# DarkPill_V1_1.net
KiCad netlist of a schematic drawn in EAGLE
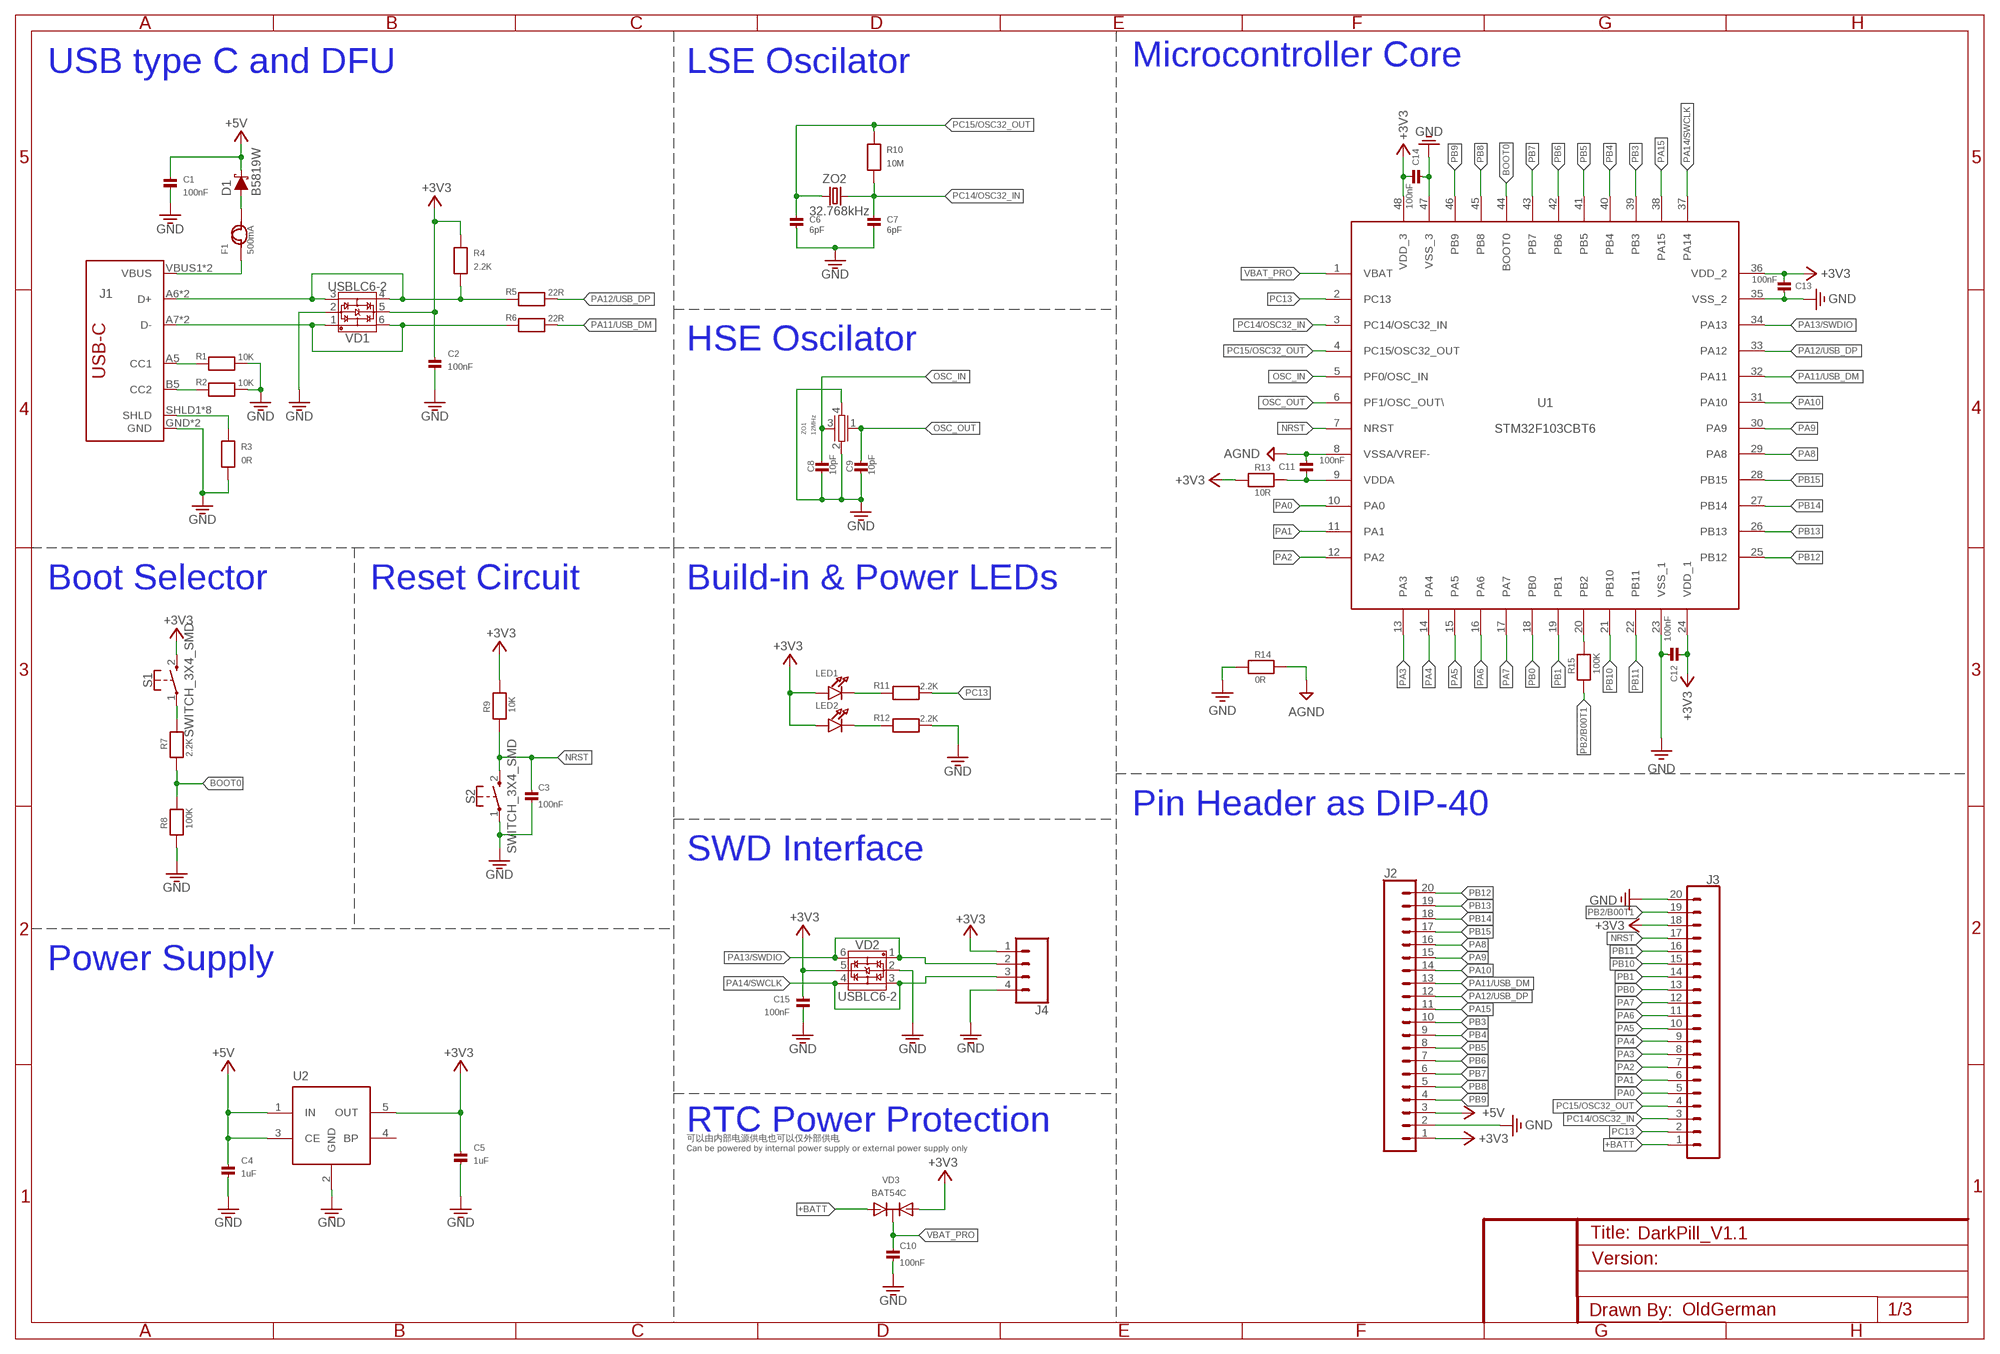
[diagram p0: schematic, sheet 1]

(export (version "E")
  (design (tool "Eeschema 10.0.6"))
  (components
    (comp (ref "C1")
      (value "100nF")
      (footprint "eagle-import:0603")
      (libsource (lib "eagle-import") (part "CAP_CERAMIC0603"))
    )
    (comp (ref "C2")
      (value "100nF")
      (footprint "eagle-import:0603")
      (libsource (lib "eagle-import") (part "CAP_CERAMIC0603"))
    )
    (comp (ref "C3")
      (value "100nF")
      (footprint "eagle-import:0603")
      (libsource (lib "eagle-import") (part "CAP_CERAMIC0603"))
    )
    (comp (ref "C4")
      (value "1uF")
      (footprint "eagle-import:0603")
      (libsource (lib "eagle-import") (part "CAP_CERAMIC0603"))
    )
    (comp (ref "C5")
      (value "1uF")
      (footprint "eagle-import:0603")
      (libsource (lib "eagle-import") (part "CAP_CERAMIC0603"))
    )
    (comp (ref "C6")
      (value "6pF")
      (footprint "eagle-import:0603")
      (libsource (lib "eagle-import") (part "CAP_CERAMIC0603"))
    )
    (comp (ref "C7")
      (value "6pF")
      (footprint "eagle-import:0603")
      (libsource (lib "eagle-import") (part "CAP_CERAMIC0603"))
    )
    (comp (ref "C8")
      (value "10pF")
      (footprint "eagle-import:0603")
      (libsource (lib "eagle-import") (part "CAP_CERAMIC0603"))
    )
    (comp (ref "C9")
      (value "10pF")
      (footprint "eagle-import:0603")
      (libsource (lib "eagle-import") (part "CAP_CERAMIC0603"))
    )
    (comp (ref "C10")
      (value "100nF")
      (footprint "eagle-import:0603")
      (libsource (lib "eagle-import") (part "CAP_CERAMIC0603"))
    )
    (comp (ref "C11")
      (value "100nF")
      (footprint "eagle-import:0603")
      (libsource (lib "eagle-import") (part "CAP_CERAMIC0603"))
    )
    (comp (ref "C12")
      (value "100nF")
      (footprint "eagle-import:0603")
      (libsource (lib "eagle-import") (part "CAP_CERAMIC0603"))
    )
    (comp (ref "C13")
      (value "100nF")
      (footprint "eagle-import:0603")
      (libsource (lib "eagle-import") (part "CAP_CERAMIC0603"))
    )
    (comp (ref "C14")
      (value "100nF")
      (footprint "eagle-import:0603")
      (libsource (lib "eagle-import") (part "CAP_CERAMIC0603"))
    )
    (comp (ref "C15")
      (value "100nF")
      (footprint "eagle-import:0603")
      (libsource (lib "eagle-import") (part "CAP_CERAMIC0603"))
    )
    (comp (ref "D1")
      (value "B5819W")
      (footprint "eagle-import:SOD-323")
      (libsource (lib "eagle-import") (part "B5819W-SOD323"))
    )
    (comp (ref "F1")
      (value "500mA")
      (footprint "eagle-import:0603")
      (libsource (lib "eagle-import") (part "FUSE"))
    )
    (comp (ref "J1")
      (value "USB_C2-LAYER")
      (footprint "eagle-import:USB-C-16P")
      (libsource (lib "eagle-import") (part "USB_C2-LAYER"))
    )
    (comp (ref "J2")
      (value "CONN_20")
      (footprint "eagle-import:1X20")
      (libsource (lib "eagle-import") (part "CONN_20"))
    )
    (comp (ref "J3")
      (value "CONN_20")
      (footprint "eagle-import:1X20")
      (libsource (lib "eagle-import") (part "CONN_20"))
    )
    (comp (ref "J4")
      (value "CONN_04PTH")
      (footprint "eagle-import:1X04")
      (libsource (lib "eagle-import") (part "CONN_04PTH"))
    )
    (comp (ref "LED1")
      (value "LED_0603_MICRO")
      (footprint "eagle-import:0603_LED")
      (libsource (lib "eagle-import") (part "LED_0603_MICRO"))
    )
    (comp (ref "LED2")
      (value "LED_0603_MICRO")
      (footprint "eagle-import:0603_LED")
      (libsource (lib "eagle-import") (part "LED_0603_MICRO"))
    )
    (comp (ref "R1")
      (value "10K")
      (footprint "eagle-import:0603")
      (libsource (lib "eagle-import") (part "RESISTOR0603"))
    )
    (comp (ref "R2")
      (value "10K")
      (footprint "eagle-import:0603")
      (libsource (lib "eagle-import") (part "RESISTOR0603"))
    )
    (comp (ref "R3")
      (value "0R")
      (footprint "eagle-import:0603")
      (libsource (lib "eagle-import") (part "RESISTOR0603"))
    )
    (comp (ref "R4")
      (value "2.2K")
      (footprint "eagle-import:0603")
      (libsource (lib "eagle-import") (part "RESISTOR0603"))
    )
    (comp (ref "R5")
      (value "22R")
      (footprint "eagle-import:0603")
      (libsource (lib "eagle-import") (part "RESISTOR0603"))
    )
    (comp (ref "R6")
      (value "22R")
      (footprint "eagle-import:0603")
      (libsource (lib "eagle-import") (part "RESISTOR0603"))
    )
    (comp (ref "R7")
      (value "2.2K")
      (footprint "eagle-import:0603")
      (libsource (lib "eagle-import") (part "RESISTOR0603"))
    )
    (comp (ref "R8")
      (value "100K")
      (footprint "eagle-import:0603")
      (libsource (lib "eagle-import") (part "RESISTOR0603"))
    )
    (comp (ref "R9")
      (value "10K")
      (footprint "eagle-import:0603")
      (libsource (lib "eagle-import") (part "RESISTOR0603"))
    )
    (comp (ref "R10")
      (value "10M")
      (footprint "eagle-import:0603")
      (libsource (lib "eagle-import") (part "RESISTOR0603"))
    )
    (comp (ref "R11")
      (value "2.2K")
      (footprint "eagle-import:0603")
      (libsource (lib "eagle-import") (part "RESISTOR0603"))
    )
    (comp (ref "R12")
      (value "2.2K")
      (footprint "eagle-import:0603")
      (libsource (lib "eagle-import") (part "RESISTOR0603"))
    )
    (comp (ref "R13")
      (value "10R")
      (footprint "eagle-import:0603")
      (libsource (lib "eagle-import") (part "RESISTOR0603"))
    )
    (comp (ref "R14")
      (value "0R")
      (footprint "eagle-import:0603")
      (libsource (lib "eagle-import") (part "RESISTOR0603"))
    )
    (comp (ref "R15")
      (value "100K")
      (footprint "eagle-import:0603")
      (libsource (lib "eagle-import") (part "RESISTOR0603"))
    )
    (comp (ref "S1")
      (value "SWITCH_3X4_SMD")
      (footprint "eagle-import:SWITCH_3X4_SMD")
      (libsource (lib "eagle-import") (part "SWITCH_3X4_SMD"))
    )
    (comp (ref "S2")
      (value "SWITCH_3X4_SMD")
      (footprint "eagle-import:SWITCH_3X4_SMD")
      (libsource (lib "eagle-import") (part "SWITCH_3X4_SMD"))
    )
    (comp (ref "U1")
      (value "STM32F103CBT6")
      (footprint "eagle-import:TQFP48")
      (libsource (lib "eagle-import") (part "STM32F303CBT6"))
    )
    (comp (ref "U2")
      (value "ME6211C33M5G-N")
      (footprint "eagle-import:SOT23-5")
      (libsource (lib "eagle-import") (part "ME6211C33M5G-N"))
    )
    (comp (ref "VD1")
      (value "USBLC6-2")
      (footprint "eagle-import:SOT23-6")
      (libsource (lib "eagle-import") (part "USBLC6-2SOT23-6"))
    )
    (comp (ref "VD2")
      (value "USBLC6-2")
      (footprint "eagle-import:SOT23-6")
      (libsource (lib "eagle-import") (part "USBLC6-2SOT23-6"))
    )
    (comp (ref "VD3")
      (value "BAT54C")
      (footprint "eagle-import:SOT23-R")
      (libsource (lib "eagle-import") (part "BAT54C"))
    )
    (comp (ref "ZO1")
      (value "12MHz")
      (footprint "eagle-import:3.2X2.5_KX-7")
      (libsource (lib "eagle-import") (part "3225_CRYSTALL"))
    )
    (comp (ref "ZO2")
      (value "32.768kHz")
      (footprint "eagle-import:3.2X1.5")
      (libsource (lib "eagle-import") (part "KX-327-NHF"))
    )
  )
  (nets
    (net (code "1") (name "+3V3") (class "Default")
      (node (ref "C12") (pin "2") (pinfunction "P$2_2") (pintype "passive"))
      (node (ref "C13") (pin "2") (pinfunction "P$2_2") (pintype "passive"))
      (node (ref "C14") (pin "2") (pinfunction "P$2_2") (pintype "passive"))
      (node (ref "C15") (pin "1") (pinfunction "P$1_1") (pintype "passive"))
      (node (ref "C2") (pin "1") (pinfunction "P$1_1") (pintype "passive"))
      (node (ref "C5") (pin "1") (pinfunction "P$1_1") (pintype "passive"))
      (node (ref "J2") (pin "1") (pinfunction "1_1") (pintype "passive"))
      (node (ref "J3") (pin "18") (pinfunction "18_18") (pintype "passive"))
      (node (ref "J4") (pin "1") (pinfunction "1_1") (pintype "passive"))
      (node (ref "LED1") (pin "1") (pinfunction "A_1") (pintype "passive"))
      (node (ref "LED2") (pin "1") (pinfunction "A_1") (pintype "passive"))
      (node (ref "R13") (pin "2") (pinfunction "2_2") (pintype "passive"))
      (node (ref "R4") (pin "2") (pinfunction "2_2") (pintype "passive"))
      (node (ref "R9") (pin "1") (pinfunction "1_1") (pintype "passive"))
      (node (ref "S1") (pin "2") (pinfunction "2_2") (pintype "passive"))
      (node (ref "U1") (pin "24") (pinfunction "VDD_1_24") (pintype "bidirectional"))
      (node (ref "U1") (pin "36") (pinfunction "VDD_2_36") (pintype "bidirectional"))
      (node (ref "U1") (pin "48") (pinfunction "VDD_3_48") (pintype "bidirectional"))
      (node (ref "U2") (pin "5") (pinfunction "OUT_5") (pintype "bidirectional"))
      (node (ref "VD1") (pin "5") (pinfunction "P$5_5") (pintype "bidirectional"))
      (node (ref "VD2") (pin "5") (pinfunction "P$5_5") (pintype "bidirectional"))
      (node (ref "VD3") (pin "1") (pinfunction "A1_1") (pintype "passive"))
    )
    (net (code "2") (name "+5V") (class "Default")
      (node (ref "C1") (pin "1") (pinfunction "P$1_1") (pintype "passive"))
      (node (ref "C4") (pin "1") (pinfunction "P$1_1") (pintype "passive"))
      (node (ref "D1") (pin "C") (pinfunction "C_C") (pintype "passive"))
      (node (ref "J2") (pin "3") (pinfunction "3_3") (pintype "passive"))
      (node (ref "U2") (pin "1") (pinfunction "IN_1") (pintype "bidirectional"))
      (node (ref "U2") (pin "3") (pinfunction "CE_3") (pintype "bidirectional"))
    )
    (net (code "3") (name "+BATT") (class "Default")
      (node (ref "J3") (pin "1") (pinfunction "1_1") (pintype "passive"))
      (node (ref "VD3") (pin "2") (pinfunction "A2_2") (pintype "passive"))
    )
    (net (code "4") (name "AGND") (class "Default")
      (node (ref "C11") (pin "1") (pinfunction "P$1_1") (pintype "passive"))
      (node (ref "R14") (pin "1") (pinfunction "1_1") (pintype "passive"))
      (node (ref "U1") (pin "8") (pinfunction "VSSA/VREF-_8") (pintype "bidirectional"))
    )
    (net (code "5") (name "BOOT0") (class "Default")
      (node (ref "R7") (pin "1") (pinfunction "1_1") (pintype "passive"))
      (node (ref "R8") (pin "1") (pinfunction "1_1") (pintype "passive"))
      (node (ref "U1") (pin "44") (pinfunction "BOOT0_44") (pintype "bidirectional"))
    )
    (net (code "6") (name "GND") (class "Default")
      (node (ref "C1") (pin "2") (pinfunction "P$2_2") (pintype "passive"))
      (node (ref "C10") (pin "2") (pinfunction "P$2_2") (pintype "passive"))
      (node (ref "C12") (pin "1") (pinfunction "P$1_1") (pintype "passive"))
      (node (ref "C13") (pin "1") (pinfunction "P$1_1") (pintype "passive"))
      (node (ref "C14") (pin "1") (pinfunction "P$1_1") (pintype "passive"))
      (node (ref "C15") (pin "2") (pinfunction "P$2_2") (pintype "passive"))
      (node (ref "C2") (pin "2") (pinfunction "P$2_2") (pintype "passive"))
      (node (ref "C3") (pin "2") (pinfunction "P$2_2") (pintype "passive"))
      (node (ref "C4") (pin "2") (pinfunction "P$2_2") (pintype "passive"))
      (node (ref "C5") (pin "2") (pinfunction "P$2_2") (pintype "passive"))
      (node (ref "C6") (pin "1") (pinfunction "P$1_1") (pintype "passive"))
      (node (ref "C7") (pin "1") (pinfunction "P$1_1") (pintype "passive"))
      (node (ref "C8") (pin "1") (pinfunction "P$1_1") (pintype "passive"))
      (node (ref "C9") (pin "1") (pinfunction "P$1_1") (pintype "passive"))
      (node (ref "J1") (pin "GND") (pinfunction "GND_GND") (pintype "bidirectional"))
      (node (ref "J1") (pin "GND2") (pinfunction "GND_GND2") (pintype "bidirectional"))
      (node (ref "J2") (pin "2") (pinfunction "2_2") (pintype "passive"))
      (node (ref "J3") (pin "20") (pinfunction "20_20") (pintype "passive"))
      (node (ref "J4") (pin "4") (pinfunction "4_4") (pintype "passive"))
      (node (ref "R1") (pin "2") (pinfunction "2_2") (pintype "passive"))
      (node (ref "R12") (pin "2") (pinfunction "2_2") (pintype "passive"))
      (node (ref "R14") (pin "2") (pinfunction "2_2") (pintype "passive"))
      (node (ref "R2") (pin "2") (pinfunction "2_2") (pintype "passive"))
      (node (ref "R3") (pin "1") (pinfunction "1_1") (pintype "passive"))
      (node (ref "R8") (pin "2") (pinfunction "2_2") (pintype "passive"))
      (node (ref "S2") (pin "1") (pinfunction "1_1") (pintype "passive"))
      (node (ref "U1") (pin "23") (pinfunction "VSS_1_23") (pintype "bidirectional"))
      (node (ref "U1") (pin "35") (pinfunction "VSS_2_35") (pintype "bidirectional"))
      (node (ref "U1") (pin "47") (pinfunction "VSS_3_47") (pintype "bidirectional"))
      (node (ref "U2") (pin "2") (pinfunction "GND_2") (pintype "bidirectional"))
      (node (ref "VD1") (pin "2") (pinfunction "P$2_2") (pintype "bidirectional"))
      (node (ref "VD2") (pin "2") (pinfunction "P$2_2") (pintype "bidirectional"))
      (node (ref "ZO1") (pin "2") (pinfunction "P$3_2") (pintype "power_in"))
      (node (ref "ZO1") (pin "4") (pinfunction "P$4_4") (pintype "power_in"))
    )
    (net (code "7") (name "NRST") (class "Default")
      (node (ref "C3") (pin "1") (pinfunction "P$1_1") (pintype "passive"))
      (node (ref "J3") (pin "17") (pinfunction "17_17") (pintype "passive"))
      (node (ref "R9") (pin "2") (pinfunction "2_2") (pintype "passive"))
      (node (ref "S2") (pin "2") (pinfunction "2_2") (pintype "passive"))
      (node (ref "U1") (pin "7") (pinfunction "NRST_7") (pintype "bidirectional"))
    )
    (net (code "8") (name "Net-(C11-P$2)") (class "Default")
      (node (ref "C11") (pin "2") (pinfunction "P$2_2") (pintype "passive"))
      (node (ref "R13") (pin "1") (pinfunction "1_1") (pintype "passive"))
      (node (ref "U1") (pin "9") (pinfunction "VDDA_9") (pintype "bidirectional"))
    )
    (net (code "9") (name "Net-(D1-PadA)") (class "Default")
      (node (ref "D1") (pin "A") (pinfunction "A_A") (pintype "passive"))
      (node (ref "F1") (pin "2") (pinfunction "2_2") (pintype "bidirectional"))
    )
    (net (code "10") (name "Net-(F1-Pad1)") (class "Default")
      (node (ref "F1") (pin "1") (pinfunction "1_1") (pintype "bidirectional"))
      (node (ref "J1") (pin "VBUS1") (pinfunction "VBUS_VBUS1") (pintype "bidirectional"))
      (node (ref "J1") (pin "VBUS2") (pinfunction "VBUS_VBUS2") (pintype "bidirectional"))
    )
    (net (code "11") (name "Net-(J1-CC1)") (class "Default")
      (node (ref "J1") (pin "A5") (pinfunction "CC1_A5") (pintype "bidirectional"))
      (node (ref "R1") (pin "1") (pinfunction "1_1") (pintype "passive"))
    )
    (net (code "12") (name "Net-(J1-CC2)") (class "Default")
      (node (ref "J1") (pin "B5") (pinfunction "CC2_B5") (pintype "bidirectional"))
      (node (ref "R2") (pin "1") (pinfunction "1_1") (pintype "passive"))
    )
    (net (code "13") (name "Net-(J1-SHLD-PadSHLD1)") (class "Default")
      (node (ref "J1") (pin "SHLD1") (pinfunction "SHLD_SHLD1") (pintype "bidirectional"))
      (node (ref "J1") (pin "SHLD2") (pinfunction "SHLD_SHLD2") (pintype "bidirectional"))
      (node (ref "J1") (pin "SHLD3") (pinfunction "SHLD_SHLD3") (pintype "bidirectional"))
      (node (ref "J1") (pin "SHLD4") (pinfunction "SHLD_SHLD4") (pintype "bidirectional"))
      (node (ref "J1") (pin "SHLD5") (pinfunction "SHLD_SHLD5") (pintype "bidirectional"))
      (node (ref "J1") (pin "SHLD6") (pinfunction "SHLD_SHLD6") (pintype "bidirectional"))
      (node (ref "J1") (pin "SHLD7") (pinfunction "SHLD_SHLD7") (pintype "bidirectional"))
      (node (ref "J1") (pin "SHLD8") (pinfunction "SHLD_SHLD8") (pintype "bidirectional"))
      (node (ref "R3") (pin "2") (pinfunction "2_2") (pintype "passive"))
    )
    (net (code "14") (name "Net-(LED1-C)") (class "Default")
      (node (ref "LED1") (pin "2") (pinfunction "C_2") (pintype "passive"))
      (node (ref "R11") (pin "1") (pinfunction "1_1") (pintype "passive"))
    )
    (net (code "15") (name "Net-(LED2-C)") (class "Default")
      (node (ref "LED2") (pin "2") (pinfunction "C_2") (pintype "passive"))
      (node (ref "R12") (pin "1") (pinfunction "1_1") (pintype "passive"))
    )
    (net (code "16") (name "Net-(R7-Pad2)") (class "Default")
      (node (ref "R7") (pin "2") (pinfunction "2_2") (pintype "passive"))
      (node (ref "S1") (pin "1") (pinfunction "1_1") (pintype "passive"))
    )
    (net (code "17") (name "Net-(U1-PB2)") (class "Default")
      (node (ref "R15") (pin "1") (pinfunction "1_1") (pintype "passive"))
      (node (ref "U1") (pin "20") (pinfunction "PB2_20") (pintype "bidirectional"))
    )
    (net (code "18") (name "Net-(VD1-P$1)") (class "Default")
      (node (ref "J1") (pin "A7") (pinfunction "D-_A7") (pintype "bidirectional"))
      (node (ref "J1") (pin "B7") (pinfunction "D-_B7") (pintype "bidirectional"))
      (node (ref "R6") (pin "1") (pinfunction "1_1") (pintype "passive"))
      (node (ref "VD1") (pin "1") (pinfunction "P$1_1") (pintype "bidirectional"))
      (node (ref "VD1") (pin "6") (pinfunction "P$6_6") (pintype "bidirectional"))
    )
    (net (code "19") (name "Net-(VD1-P$3)") (class "Default")
      (node (ref "J1") (pin "A6") (pinfunction "D+_A6") (pintype "bidirectional"))
      (node (ref "J1") (pin "B6") (pinfunction "D+_B6") (pintype "bidirectional"))
      (node (ref "R4") (pin "1") (pinfunction "1_1") (pintype "passive"))
      (node (ref "R5") (pin "1") (pinfunction "1_1") (pintype "passive"))
      (node (ref "VD1") (pin "3") (pinfunction "P$3_3") (pintype "bidirectional"))
      (node (ref "VD1") (pin "4") (pinfunction "P$4_4") (pintype "bidirectional"))
    )
    (net (code "20") (name "OSC_IN") (class "Default")
      (node (ref "C8") (pin "2") (pinfunction "P$2_2") (pintype "passive"))
      (node (ref "U1") (pin "5") (pinfunction "PF0/OSC_IN_5") (pintype "bidirectional"))
      (node (ref "ZO1") (pin "3") (pinfunction "P$2_3") (pintype "bidirectional"))
    )
    (net (code "21") (name "OSC_OUT") (class "Default")
      (node (ref "C9") (pin "2") (pinfunction "P$2_2") (pintype "passive"))
      (node (ref "U1") (pin "6") (pinfunction "PF1/OSC_OUT\\_6") (pintype "bidirectional"))
      (node (ref "ZO1") (pin "1") (pinfunction "P$1_1") (pintype "bidirectional"))
    )
    (net (code "22") (name "PA0") (class "Default")
      (node (ref "J3") (pin "5") (pinfunction "5_5") (pintype "passive"))
      (node (ref "U1") (pin "10") (pinfunction "PA0_10") (pintype "bidirectional"))
    )
    (net (code "23") (name "PA1") (class "Default")
      (node (ref "J3") (pin "6") (pinfunction "6_6") (pintype "passive"))
      (node (ref "U1") (pin "11") (pinfunction "PA1_11") (pintype "bidirectional"))
    )
    (net (code "24") (name "PA2") (class "Default")
      (node (ref "J3") (pin "7") (pinfunction "7_7") (pintype "passive"))
      (node (ref "U1") (pin "12") (pinfunction "PA2_12") (pintype "bidirectional"))
    )
    (net (code "25") (name "PA3") (class "Default")
      (node (ref "J3") (pin "8") (pinfunction "8_8") (pintype "passive"))
      (node (ref "U1") (pin "13") (pinfunction "PA3_13") (pintype "bidirectional"))
    )
    (net (code "26") (name "PA4") (class "Default")
      (node (ref "J3") (pin "9") (pinfunction "9_9") (pintype "passive"))
      (node (ref "U1") (pin "14") (pinfunction "PA4_14") (pintype "bidirectional"))
    )
    (net (code "27") (name "PA5") (class "Default")
      (node (ref "J3") (pin "10") (pinfunction "10_10") (pintype "passive"))
      (node (ref "U1") (pin "15") (pinfunction "PA5_15") (pintype "bidirectional"))
    )
    (net (code "28") (name "PA6") (class "Default")
      (node (ref "J3") (pin "11") (pinfunction "11_11") (pintype "passive"))
      (node (ref "U1") (pin "16") (pinfunction "PA6_16") (pintype "bidirectional"))
    )
    (net (code "29") (name "PA7") (class "Default")
      (node (ref "J3") (pin "12") (pinfunction "12_12") (pintype "passive"))
      (node (ref "U1") (pin "17") (pinfunction "PA7_17") (pintype "bidirectional"))
    )
    (net (code "30") (name "PA8") (class "Default")
      (node (ref "J2") (pin "16") (pinfunction "16_16") (pintype "passive"))
      (node (ref "U1") (pin "29") (pinfunction "PA8_29") (pintype "bidirectional"))
    )
    (net (code "31") (name "PA9") (class "Default")
      (node (ref "J2") (pin "15") (pinfunction "15_15") (pintype "passive"))
      (node (ref "U1") (pin "30") (pinfunction "PA9_30") (pintype "bidirectional"))
    )
    (net (code "32") (name "PA10") (class "Default")
      (node (ref "J2") (pin "14") (pinfunction "14_14") (pintype "passive"))
      (node (ref "U1") (pin "31") (pinfunction "PA10_31") (pintype "bidirectional"))
    )
    (net (code "33") (name "PA11{slash}USB_DM") (class "Default")
      (node (ref "J2") (pin "13") (pinfunction "13_13") (pintype "passive"))
      (node (ref "R6") (pin "2") (pinfunction "2_2") (pintype "passive"))
      (node (ref "U1") (pin "32") (pinfunction "PA11_32") (pintype "bidirectional"))
    )
    (net (code "34") (name "PA12{slash}USB_DP") (class "Default")
      (node (ref "J2") (pin "12") (pinfunction "12_12") (pintype "passive"))
      (node (ref "R5") (pin "2") (pinfunction "2_2") (pintype "passive"))
      (node (ref "U1") (pin "33") (pinfunction "PA12_33") (pintype "bidirectional"))
    )
    (net (code "35") (name "PA13{slash}SWDIO") (class "Default")
      (node (ref "J4") (pin "2") (pinfunction "2_2") (pintype "passive"))
      (node (ref "U1") (pin "34") (pinfunction "PA13_34") (pintype "bidirectional"))
      (node (ref "VD2") (pin "1") (pinfunction "P$1_1") (pintype "bidirectional"))
      (node (ref "VD2") (pin "6") (pinfunction "P$6_6") (pintype "bidirectional"))
    )
    (net (code "36") (name "PA14{slash}SWCLK") (class "Default")
      (node (ref "J4") (pin "3") (pinfunction "3_3") (pintype "passive"))
      (node (ref "U1") (pin "37") (pinfunction "PA14_37") (pintype "bidirectional"))
      (node (ref "VD2") (pin "3") (pinfunction "P$3_3") (pintype "bidirectional"))
      (node (ref "VD2") (pin "4") (pinfunction "P$4_4") (pintype "bidirectional"))
    )
    (net (code "37") (name "PA15") (class "Default")
      (node (ref "J2") (pin "11") (pinfunction "11_11") (pintype "passive"))
      (node (ref "U1") (pin "38") (pinfunction "PA15_38") (pintype "bidirectional"))
    )
    (net (code "38") (name "PB0") (class "Default")
      (node (ref "J3") (pin "13") (pinfunction "13_13") (pintype "passive"))
      (node (ref "U1") (pin "18") (pinfunction "PB0_18") (pintype "bidirectional"))
    )
    (net (code "39") (name "PB1") (class "Default")
      (node (ref "J3") (pin "14") (pinfunction "14_14") (pintype "passive"))
      (node (ref "U1") (pin "19") (pinfunction "PB1_19") (pintype "bidirectional"))
    )
    (net (code "40") (name "PB2{slash}B00T1") (class "Default")
      (node (ref "J3") (pin "19") (pinfunction "19_19") (pintype "passive"))
      (node (ref "R15") (pin "2") (pinfunction "2_2") (pintype "passive"))
    )
    (net (code "41") (name "PB3") (class "Default")
      (node (ref "J2") (pin "10") (pinfunction "10_10") (pintype "passive"))
      (node (ref "U1") (pin "39") (pinfunction "PB3_39") (pintype "bidirectional"))
    )
    (net (code "42") (name "PB4") (class "Default")
      (node (ref "J2") (pin "9") (pinfunction "9_9") (pintype "passive"))
      (node (ref "U1") (pin "40") (pinfunction "PB4_40") (pintype "bidirectional"))
    )
    (net (code "43") (name "PB5") (class "Default")
      (node (ref "J2") (pin "8") (pinfunction "8_8") (pintype "passive"))
      (node (ref "U1") (pin "41") (pinfunction "PB5_41") (pintype "bidirectional"))
    )
    (net (code "44") (name "PB6") (class "Default")
      (node (ref "J2") (pin "7") (pinfunction "7_7") (pintype "passive"))
      (node (ref "U1") (pin "42") (pinfunction "PB6_42") (pintype "bidirectional"))
    )
    (net (code "45") (name "PB7") (class "Default")
      (node (ref "J2") (pin "6") (pinfunction "6_6") (pintype "passive"))
      (node (ref "U1") (pin "43") (pinfunction "PB7_43") (pintype "bidirectional"))
    )
    (net (code "46") (name "PB8") (class "Default")
      (node (ref "J2") (pin "5") (pinfunction "5_5") (pintype "passive"))
      (node (ref "U1") (pin "45") (pinfunction "PB8_45") (pintype "bidirectional"))
    )
    (net (code "47") (name "PB9") (class "Default")
      (node (ref "J2") (pin "4") (pinfunction "4_4") (pintype "passive"))
      (node (ref "U1") (pin "46") (pinfunction "PB9_46") (pintype "bidirectional"))
    )
    (net (code "48") (name "PB10") (class "Default")
      (node (ref "J3") (pin "15") (pinfunction "15_15") (pintype "passive"))
      (node (ref "U1") (pin "21") (pinfunction "PB10_21") (pintype "bidirectional"))
    )
    (net (code "49") (name "PB11") (class "Default")
      (node (ref "J3") (pin "16") (pinfunction "16_16") (pintype "passive"))
      (node (ref "U1") (pin "22") (pinfunction "PB11_22") (pintype "bidirectional"))
    )
    (net (code "50") (name "PB12") (class "Default")
      (node (ref "J2") (pin "20") (pinfunction "20_20") (pintype "passive"))
      (node (ref "U1") (pin "25") (pinfunction "PB12_25") (pintype "bidirectional"))
    )
    (net (code "51") (name "PB13") (class "Default")
      (node (ref "J2") (pin "19") (pinfunction "19_19") (pintype "passive"))
      (node (ref "U1") (pin "26") (pinfunction "PB13_26") (pintype "bidirectional"))
    )
    (net (code "52") (name "PB14") (class "Default")
      (node (ref "J2") (pin "18") (pinfunction "18_18") (pintype "passive"))
      (node (ref "U1") (pin "27") (pinfunction "PB14_27") (pintype "bidirectional"))
    )
    (net (code "53") (name "PB15") (class "Default")
      (node (ref "J2") (pin "17") (pinfunction "17_17") (pintype "passive"))
      (node (ref "U1") (pin "28") (pinfunction "PB15_28") (pintype "bidirectional"))
    )
    (net (code "54") (name "PC13") (class "Default")
      (node (ref "J3") (pin "2") (pinfunction "2_2") (pintype "passive"))
      (node (ref "R11") (pin "2") (pinfunction "2_2") (pintype "passive"))
      (node (ref "U1") (pin "2") (pinfunction "PC13_2") (pintype "bidirectional"))
    )
    (net (code "55") (name "PC14{slash}OSC32_IN") (class "Default")
      (node (ref "C7") (pin "2") (pinfunction "P$2_2") (pintype "passive"))
      (node (ref "J3") (pin "3") (pinfunction "3_3") (pintype "passive"))
      (node (ref "R10") (pin "2") (pinfunction "2_2") (pintype "passive"))
      (node (ref "U1") (pin "3") (pinfunction "PC14/OSC32_IN_3") (pintype "bidirectional"))
      (node (ref "ZO2") (pin "2") (pinfunction "2_2") (pintype "passive"))
    )
    (net (code "56") (name "PC15{slash}OSC32_OUT") (class "Default")
      (node (ref "C6") (pin "2") (pinfunction "P$2_2") (pintype "passive"))
      (node (ref "J3") (pin "4") (pinfunction "4_4") (pintype "passive"))
      (node (ref "R10") (pin "1") (pinfunction "1_1") (pintype "passive"))
      (node (ref "U1") (pin "4") (pinfunction "PC15/OSC32_OUT_4") (pintype "bidirectional"))
      (node (ref "ZO2") (pin "1") (pinfunction "1_1") (pintype "passive"))
    )
    (net (code "57") (name "VBAT_PRO") (class "Default")
      (node (ref "C10") (pin "1") (pinfunction "P$1_1") (pintype "passive"))
      (node (ref "U1") (pin "1") (pinfunction "VBAT_1") (pintype "bidirectional"))
      (node (ref "VD3") (pin "3") (pinfunction "C_3") (pintype "passive"))
    )
    (net (code "58") (name "unconnected-(U2-BP-Pad4)") (class "Default")
      (node (ref "U2") (pin "4") (pinfunction "BP_4") (pintype "bidirectional"))
    )
  )
)
